# Cassiopea.net
KiCad netlist of a schematic drawn in EAGLE
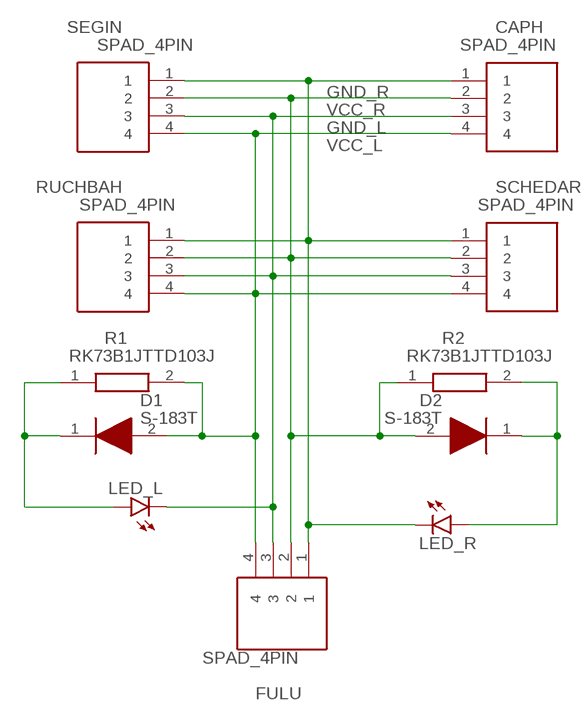
[diagram p0: schematic, sheet 1]

(export (version "E")
  (design (tool "Eeschema 10.0.6"))
  (components
    (comp (ref "CAPH")
      (value "SPAD_4PIN")
      (footprint "eagle-import:SAPD_4PIN")
      (fields (field (name "MANUFACTURER_PART_NUMBER") "S4B-XH-A(LF)(SN)"))
      (libsource (lib "eagle-import") (part "SPAD_4PIN"))
    )
    (comp (ref "D1")
      (value "S-183T")
      (footprint "eagle-import:SODFL3516X70N")
      (fields (field (name "MOUSER_PART_NUMBER") "954-S-183T"))
      (libsource (lib "eagle-import") (part "S-183T"))
    )
    (comp (ref "D2")
      (value "S-183T")
      (footprint "eagle-import:SODFL3516X70N")
      (fields (field (name "MOUSER_PART_NUMBER") "954-S-183T"))
      (libsource (lib "eagle-import") (part "S-183T"))
    )
    (comp (ref "FULU")
      (value "SPAD_4PIN")
      (footprint "eagle-import:SAPD_4PIN")
      (fields (field (name "MANUFACTURER_PART_NUMBER") "S4B-XH-A(LF)(SN)"))
      (libsource (lib "eagle-import") (part "SPAD_4PIN"))
    )
    (comp (ref "LED_L")
      (value "LEDB155")
      (footprint "eagle-import:LED_FOOT")
      (libsource (lib "eagle-import") (part "LEDB155"))
    )
    (comp (ref "LED_R")
      (value "LEDB155")
      (footprint "eagle-import:LED_FOOT")
      (libsource (lib "eagle-import") (part "LEDB155"))
    )
    (comp (ref "R1")
      (value "RK73B1JTTD103J")
      (footprint "eagle-import:RESC1608X55N")
      (fields (field (name "MOUSER_PART_NUMBER") "660-RK73B1JTTD103J"))
      (libsource (lib "eagle-import") (part "RK73B1JTTD103J"))
    )
    (comp (ref "R2")
      (value "RK73B1JTTD103J")
      (footprint "eagle-import:RESC1608X55N")
      (fields (field (name "MOUSER_PART_NUMBER") "660-RK73B1JTTD103J"))
      (libsource (lib "eagle-import") (part "RK73B1JTTD103J"))
    )
    (comp (ref "RUCHBAH")
      (value "SPAD_4PIN")
      (footprint "eagle-import:SAPD_4PIN")
      (fields (field (name "MANUFACTURER_PART_NUMBER") "S4B-XH-A(LF)(SN)"))
      (libsource (lib "eagle-import") (part "SPAD_4PIN"))
    )
    (comp (ref "SCHEDAR")
      (value "SPAD_4PIN")
      (footprint "eagle-import:SAPD_4PIN")
      (fields (field (name "MANUFACTURER_PART_NUMBER") "S4B-XH-A(LF)(SN)"))
      (libsource (lib "eagle-import") (part "SPAD_4PIN"))
    )
    (comp (ref "SEGIN")
      (value "SPAD_4PIN")
      (footprint "eagle-import:SAPD_4PIN")
      (fields (field (name "MANUFACTURER_PART_NUMBER") "S4B-XH-A(LF)(SN)"))
      (libsource (lib "eagle-import") (part "SPAD_4PIN"))
    )
  )
  (nets
    (net (code "1") (name "/GND_L") (class "Default")
      (node (ref "CAPH") (pin "3") (pinfunction "3_3") (pintype "bidirectional"))
      (node (ref "FULU") (pin "3") (pinfunction "3_3") (pintype "bidirectional"))
      (node (ref "LED_L") (pin "K") (pinfunction "C_K") (pintype "passive"))
      (node (ref "RUCHBAH") (pin "3") (pinfunction "3_3") (pintype "bidirectional"))
      (node (ref "SCHEDAR") (pin "3") (pinfunction "3_3") (pintype "bidirectional"))
      (node (ref "SEGIN") (pin "3") (pinfunction "3_3") (pintype "bidirectional"))
    )
    (net (code "2") (name "/GND_R") (class "Default")
      (node (ref "CAPH") (pin "1") (pinfunction "1_1") (pintype "bidirectional"))
      (node (ref "FULU") (pin "1") (pinfunction "1_1") (pintype "bidirectional"))
      (node (ref "LED_R") (pin "K") (pinfunction "C_K") (pintype "passive"))
      (node (ref "RUCHBAH") (pin "1") (pinfunction "1_1") (pintype "bidirectional"))
      (node (ref "SCHEDAR") (pin "1") (pinfunction "1_1") (pintype "bidirectional"))
      (node (ref "SEGIN") (pin "1") (pinfunction "1_1") (pintype "bidirectional"))
    )
    (net (code "3") (name "/VCC_L") (class "Default")
      (node (ref "CAPH") (pin "4") (pinfunction "4_4") (pintype "bidirectional"))
      (node (ref "D1") (pin "2") (pinfunction "A_2") (pintype "bidirectional"))
      (node (ref "FULU") (pin "4") (pinfunction "4_4") (pintype "bidirectional"))
      (node (ref "R1") (pin "2") (pinfunction "2_2") (pintype "bidirectional"))
      (node (ref "RUCHBAH") (pin "4") (pinfunction "4_4") (pintype "bidirectional"))
      (node (ref "SCHEDAR") (pin "4") (pinfunction "4_4") (pintype "bidirectional"))
      (node (ref "SEGIN") (pin "4") (pinfunction "4_4") (pintype "bidirectional"))
    )
    (net (code "4") (name "/VCC_R") (class "Default")
      (node (ref "CAPH") (pin "2") (pinfunction "2_2") (pintype "bidirectional"))
      (node (ref "D2") (pin "2") (pinfunction "A_2") (pintype "bidirectional"))
      (node (ref "FULU") (pin "2") (pinfunction "2_2") (pintype "bidirectional"))
      (node (ref "R2") (pin "1") (pinfunction "1_1") (pintype "bidirectional"))
      (node (ref "RUCHBAH") (pin "2") (pinfunction "2_2") (pintype "bidirectional"))
      (node (ref "SCHEDAR") (pin "2") (pinfunction "2_2") (pintype "bidirectional"))
      (node (ref "SEGIN") (pin "2") (pinfunction "2_2") (pintype "bidirectional"))
    )
    (net (code "5") (name "Net-(D1-K)") (class "Default")
      (node (ref "D1") (pin "1") (pinfunction "K_1") (pintype "bidirectional"))
      (node (ref "LED_L") (pin "A") (pinfunction "A_A") (pintype "passive"))
      (node (ref "R1") (pin "1") (pinfunction "1_1") (pintype "bidirectional"))
    )
    (net (code "6") (name "Net-(D2-K)") (class "Default")
      (node (ref "D2") (pin "1") (pinfunction "K_1") (pintype "bidirectional"))
      (node (ref "LED_R") (pin "A") (pinfunction "A_A") (pintype "passive"))
      (node (ref "R2") (pin "2") (pinfunction "2_2") (pintype "bidirectional"))
    )
  )
)
